# Firefly-Top.net
KiCad netlist of a schematic drawn in EAGLE
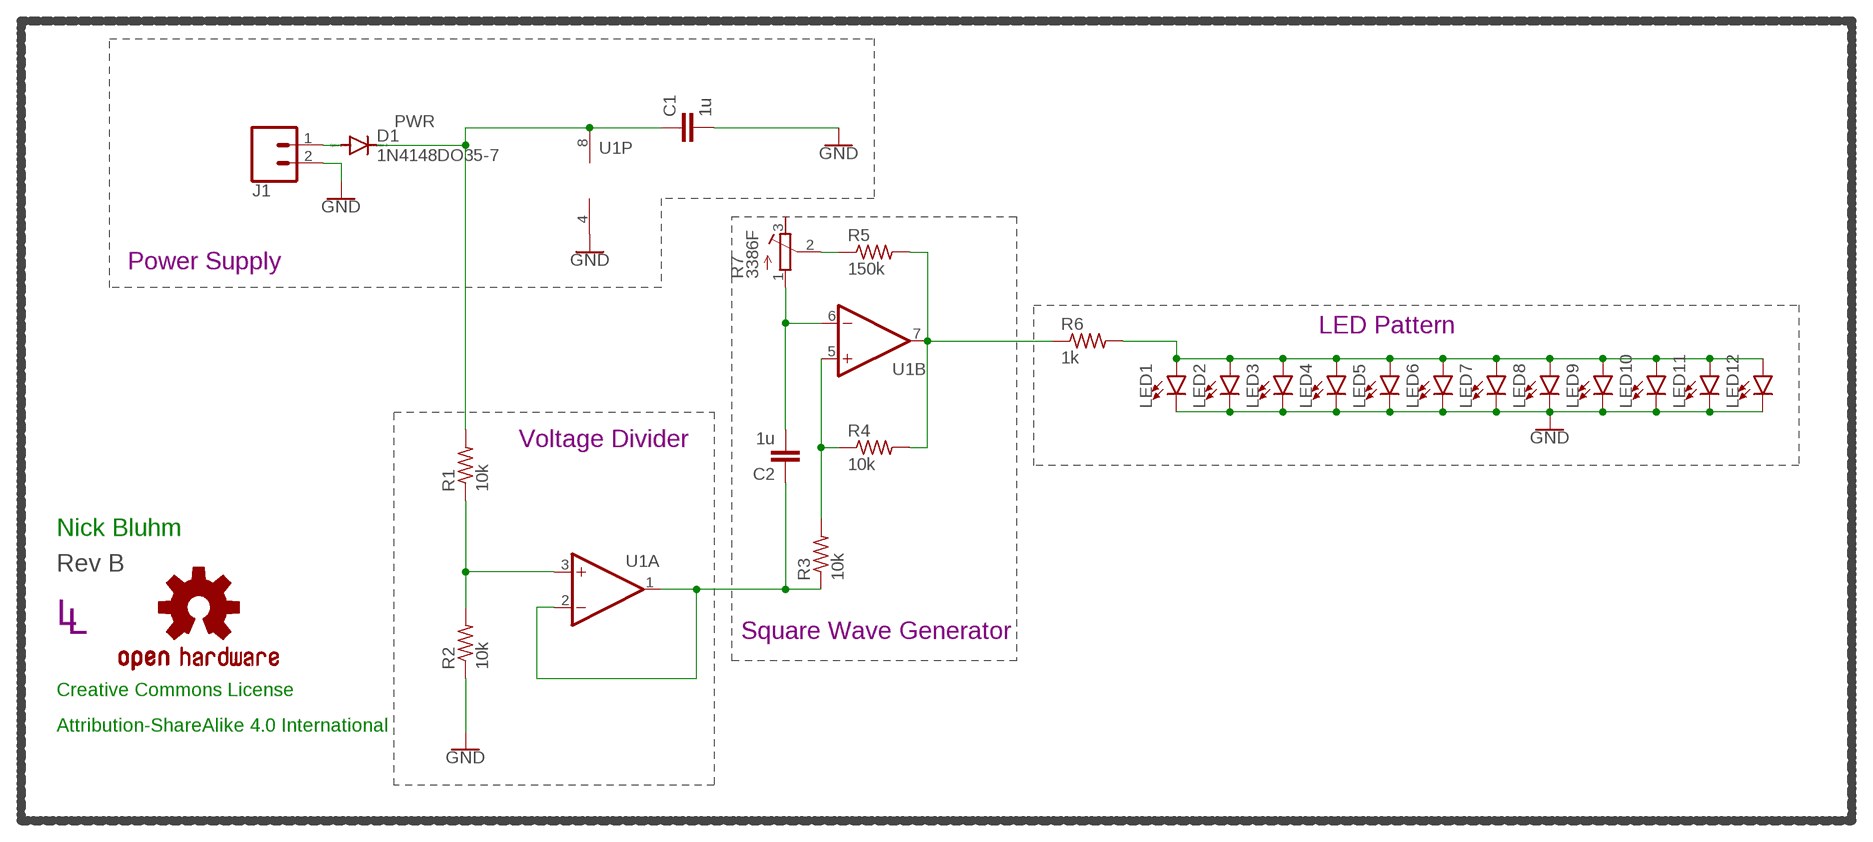
[diagram p0: schematic, sheet 1]

(export (version "E")
  (design (tool "Eeschema 10.0.6"))
  (components
    (comp (ref "C1")
      (value "1u")
      (footprint "eagle-import:C0805")
      (libsource (lib "eagle-import") (part "CAPACITOR0805"))
    )
    (comp (ref "C2")
      (value "1u")
      (footprint "eagle-import:C0805")
      (libsource (lib "eagle-import") (part "CAPACITOR0805"))
    )
    (comp (ref "D1")
      (value "1N4148DO35-7")
      (footprint "eagle-import:DO35-7")
      (libsource (lib "eagle-import") (part "1N4148DO35-7"))
    )
    (comp (ref "J1")
      (value "CONN_02")
      (footprint "eagle-import:1X02")
      (libsource (lib "eagle-import") (part "CONN_02"))
    )
    (comp (ref "LED1")
      (value "LED5MM")
      (footprint "eagle-import:LED_5MM")
      (libsource (lib "eagle-import") (part "LED5MM"))
    )
    (comp (ref "LED2")
      (value "LED5MM")
      (footprint "eagle-import:LED_5MM")
      (libsource (lib "eagle-import") (part "LED5MM"))
    )
    (comp (ref "LED3")
      (value "LED5MM")
      (footprint "eagle-import:LED_5MM")
      (libsource (lib "eagle-import") (part "LED5MM"))
    )
    (comp (ref "LED4")
      (value "LED5MM")
      (footprint "eagle-import:LED_5MM")
      (libsource (lib "eagle-import") (part "LED5MM"))
    )
    (comp (ref "LED5")
      (value "LED5MM")
      (footprint "eagle-import:LED_5MM")
      (libsource (lib "eagle-import") (part "LED5MM"))
    )
    (comp (ref "LED6")
      (value "LED5MM")
      (footprint "eagle-import:LED_5MM")
      (libsource (lib "eagle-import") (part "LED5MM"))
    )
    (comp (ref "LED7")
      (value "LED5MM")
      (footprint "eagle-import:LED_5MM")
      (libsource (lib "eagle-import") (part "LED5MM"))
    )
    (comp (ref "LED8")
      (value "LED5MM")
      (footprint "eagle-import:LED_5MM")
      (libsource (lib "eagle-import") (part "LED5MM"))
    )
    (comp (ref "LED9")
      (value "LED5MM")
      (footprint "eagle-import:LED_5MM")
      (libsource (lib "eagle-import") (part "LED5MM"))
    )
    (comp (ref "LED10")
      (value "LED5MM")
      (footprint "eagle-import:LED_5MM")
      (libsource (lib "eagle-import") (part "LED5MM"))
    )
    (comp (ref "LED11")
      (value "LED5MM")
      (footprint "eagle-import:LED_5MM")
      (libsource (lib "eagle-import") (part "LED5MM"))
    )
    (comp (ref "LED12")
      (value "LED5MM")
      (footprint "eagle-import:LED_5MM")
      (libsource (lib "eagle-import") (part "LED5MM"))
    )
    (comp (ref "LOGO1")
      (value "OSHW-LOGOL")
      (footprint "eagle-import:OSHW-LOGO-L")
      (libsource (lib "eagle-import") (part "OSHW-LOGOL"))
    )
    (comp (ref "R1")
      (value "10k")
      (footprint "eagle-import:R0805")
      (libsource (lib "eagle-import") (part "RESISTOR0805"))
    )
    (comp (ref "R2")
      (value "10k")
      (footprint "eagle-import:R0805")
      (libsource (lib "eagle-import") (part "RESISTOR0805"))
    )
    (comp (ref "R3")
      (value "10k")
      (footprint "eagle-import:R0805")
      (libsource (lib "eagle-import") (part "RESISTOR0805"))
    )
    (comp (ref "R4")
      (value "10k")
      (footprint "eagle-import:R0805")
      (libsource (lib "eagle-import") (part "RESISTOR0805"))
    )
    (comp (ref "R5")
      (value "150k")
      (footprint "eagle-import:R0805")
      (libsource (lib "eagle-import") (part "RESISTOR0805"))
    )
    (comp (ref "R6")
      (value "1k")
      (footprint "eagle-import:R0805")
      (libsource (lib "eagle-import") (part "RESISTOR0805"))
    )
    (comp (ref "R7")
      (value "3386F")
      (footprint "eagle-import:3386F-FOOTPRINT")
      (libsource (lib "eagle-import") (part "3386F"))
    )
    (comp (ref "U$4")
      (value "REVISION.B")
      (footprint "eagle-import:REV.B")
      (libsource (lib "eagle-import") (part "REVISION.B"))
    )
    (comp (ref "U$5")
      (value "LINNES.LAB.LOGO")
      (footprint "eagle-import:LINNES.LAB.LOGO")
      (libsource (lib "eagle-import") (part "LINNES.LAB.LOGO"))
    )
    (comp (ref "U1")
      (value "OP-DUALMCP6002R")
      (footprint "eagle-import:SO8")
      (fields (field (name "MF") "Microchip Technology") (field (name "MPN") "MCP6002T-I/SN"))
      (libsource (lib "eagle-import") (part "OP-DUALRMCP6002"))
    )
  )
  (nets
    (net (code "1") (name "/PWR") (class "Default")
      (node (ref "C1") (pin "1") (pinfunction "1_1") (pintype "passive"))
      (node (ref "D1") (pin "C") (pinfunction "C_C") (pintype "passive"))
      (node (ref "R1") (pin "2") (pinfunction "2_2") (pintype "passive"))
      (node (ref "U1") (pin "8") (pinfunction "V+_8") (pintype "power_in"))
    )
    (net (code "2") (name "GND") (class "Default")
      (node (ref "C1") (pin "2") (pinfunction "2_2") (pintype "passive"))
      (node (ref "J1") (pin "2") (pinfunction "2_2") (pintype "passive"))
      (node (ref "LED1") (pin "K") (pinfunction "C_K") (pintype "passive"))
      (node (ref "LED10") (pin "K") (pinfunction "C_K") (pintype "passive"))
      (node (ref "LED11") (pin "K") (pinfunction "C_K") (pintype "passive"))
      (node (ref "LED12") (pin "K") (pinfunction "C_K") (pintype "passive"))
      (node (ref "LED2") (pin "K") (pinfunction "C_K") (pintype "passive"))
      (node (ref "LED3") (pin "K") (pinfunction "C_K") (pintype "passive"))
      (node (ref "LED4") (pin "K") (pinfunction "C_K") (pintype "passive"))
      (node (ref "LED5") (pin "K") (pinfunction "C_K") (pintype "passive"))
      (node (ref "LED6") (pin "K") (pinfunction "C_K") (pintype "passive"))
      (node (ref "LED7") (pin "K") (pinfunction "C_K") (pintype "passive"))
      (node (ref "LED8") (pin "K") (pinfunction "C_K") (pintype "passive"))
      (node (ref "LED9") (pin "K") (pinfunction "C_K") (pintype "passive"))
      (node (ref "R2") (pin "1") (pinfunction "1_1") (pintype "passive"))
      (node (ref "U1") (pin "4") (pinfunction "V-_4") (pintype "power_in"))
    )
    (net (code "3") (name "Net-(D1-PadA)") (class "Default")
      (node (ref "D1") (pin "A") (pinfunction "A_A") (pintype "passive"))
      (node (ref "J1") (pin "1") (pinfunction "1_1") (pintype "passive"))
    )
    (net (code "4") (name "Net-(LED1-PadA)") (class "Default")
      (node (ref "LED1") (pin "A") (pinfunction "A_A") (pintype "passive"))
      (node (ref "LED10") (pin "A") (pinfunction "A_A") (pintype "passive"))
      (node (ref "LED11") (pin "A") (pinfunction "A_A") (pintype "passive"))
      (node (ref "LED12") (pin "A") (pinfunction "A_A") (pintype "passive"))
      (node (ref "LED2") (pin "A") (pinfunction "A_A") (pintype "passive"))
      (node (ref "LED3") (pin "A") (pinfunction "A_A") (pintype "passive"))
      (node (ref "LED4") (pin "A") (pinfunction "A_A") (pintype "passive"))
      (node (ref "LED5") (pin "A") (pinfunction "A_A") (pintype "passive"))
      (node (ref "LED6") (pin "A") (pinfunction "A_A") (pintype "passive"))
      (node (ref "LED7") (pin "A") (pinfunction "A_A") (pintype "passive"))
      (node (ref "LED8") (pin "A") (pinfunction "A_A") (pintype "passive"))
      (node (ref "LED9") (pin "A") (pinfunction "A_A") (pintype "passive"))
      (node (ref "R6") (pin "2") (pinfunction "2_2") (pintype "passive"))
    )
    (net (code "5") (name "Net-(R7-A)") (class "Default")
      (node (ref "C2") (pin "2") (pinfunction "2_2") (pintype "passive"))
      (node (ref "R7") (pin "1") (pinfunction "A_1") (pintype "passive"))
      (node (ref "U1") (pin "6") (pinfunction "-IN_6") (pintype "input"))
    )
    (net (code "6") (name "Net-(R7-W)") (class "Default")
      (node (ref "R5") (pin "1") (pinfunction "1_1") (pintype "passive"))
      (node (ref "R7") (pin "2") (pinfunction "W_2") (pintype "passive"))
    )
    (net (code "7") (name "Net-(U1A-+IN)") (class "Default")
      (node (ref "R1") (pin "1") (pinfunction "1_1") (pintype "passive"))
      (node (ref "R2") (pin "2") (pinfunction "2_2") (pintype "passive"))
      (node (ref "U1") (pin "3") (pinfunction "+IN_3") (pintype "input"))
    )
    (net (code "8") (name "Net-(U1A--IN)") (class "Default")
      (node (ref "C2") (pin "1") (pinfunction "1_1") (pintype "passive"))
      (node (ref "R3") (pin "1") (pinfunction "1_1") (pintype "passive"))
      (node (ref "U1") (pin "1") (pinfunction "OUT_1") (pintype "output"))
      (node (ref "U1") (pin "2") (pinfunction "-IN_2") (pintype "input"))
    )
    (net (code "9") (name "Net-(U1B-+IN)") (class "Default")
      (node (ref "R3") (pin "2") (pinfunction "2_2") (pintype "passive"))
      (node (ref "R4") (pin "1") (pinfunction "1_1") (pintype "passive"))
      (node (ref "U1") (pin "5") (pinfunction "+IN_5") (pintype "input"))
    )
    (net (code "10") (name "Net-(U1B-OUT)") (class "Default")
      (node (ref "R4") (pin "2") (pinfunction "2_2") (pintype "passive"))
      (node (ref "R5") (pin "2") (pinfunction "2_2") (pintype "passive"))
      (node (ref "R6") (pin "1") (pinfunction "1_1") (pintype "passive"))
      (node (ref "U1") (pin "7") (pinfunction "OUT_7") (pintype "output"))
    )
    (net (code "11") (name "unconnected-(R7-E-Pad3)") (class "Default")
      (node (ref "R7") (pin "3") (pinfunction "E_3") (pintype "passive"))
    )
  )
)
